# ADC.net
KiCad netlist of a schematic drawn in Altium Designer
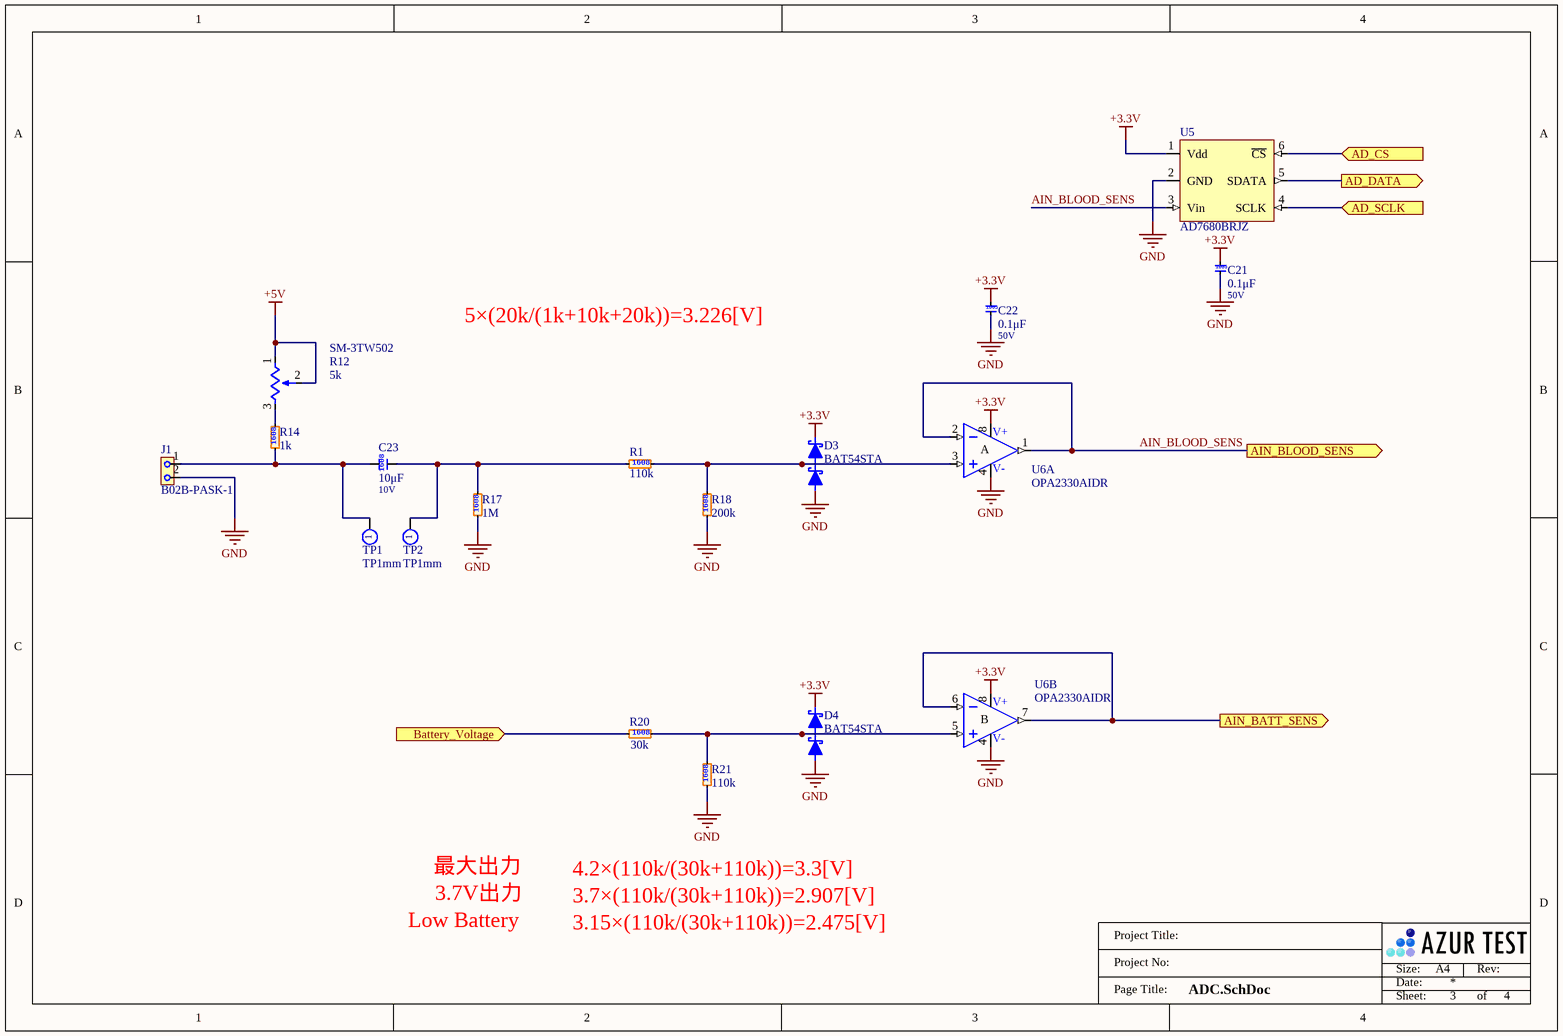
[diagram p0: ADC.SchDoc]

(export (version "E")
  (design (tool "Eeschema 10.0.6"))
  (components
    (comp (ref "C21")
      (value "GRM1552C1H101J")
      (footprint "C1005")
      (description "セラコン1005サイズ")
      (fields (field (name "TAG") "0.1μF") (field (name "VOLTAGE") "50V"))
      (libsource (lib "SSST") (part "C1005"))
    )
    (comp (ref "C22")
      (value "GRM1552C1H101J")
      (footprint "C1005")
      (description "セラコン1005サイズ")
      (fields (field (name "TAG") "0.1μF") (field (name "VOLTAGE") "50V"))
      (libsource (lib "SSST") (part "C1005"))
    )
    (comp (ref "C23")
      (value "C1608X5R1A106M080AC")
      (footprint "C1608")
      (description "セラコン1608サイズ")
      (fields (field (name "TAG") "10μF") (field (name "VOLTAGE") "10V"))
      (libsource (lib "Isoretion wear meater") (part "C1608"))
    )
    (comp (ref "D3")
      (value "BAT54STA")
      (footprint "SOT-23")
      (description "ダブル直列ショットキー")
      (libsource (lib "SSST") (part "BAT54S"))
    )
    (comp (ref "D4")
      (value "BAT54STA")
      (footprint "SOT-23")
      (description "ダブル直列ショットキー")
      (libsource (lib "SSST") (part "BAT54S"))
    )
    (comp (ref "J1")
      (value "B02B-PASK-1")
      (footprint "B02B-PASK-1")
      (description "雄,ストレート,1列2ピン")
      (libsource (lib "SSST") (part "B02B-PASK-1"))
    )
    (comp (ref "R1")
      (value "RG1608P-114-B-T5")
      (footprint "R1608")
      (description "薄膜チップ抵抗1608サイズ")
      (fields (field (name "TAG") "110k"))
      (libsource (lib "") (part "MF1608_1"))
    )
    (comp (ref "R12")
      (value "SM-3TW502")
      (footprint "SM-3TW")
      (description "CERMET TRIMMER 11 turns Top adjustmet")
      (fields (field (name "TAG") "5k"))
      (libsource (lib "SSST") (part "SM-3TW***"))
    )
    (comp (ref "R14")
      (value "RG1608P-102-B-T5")
      (footprint "R1608")
      (description "薄膜チップ抵抗1608サイズ")
      (fields (field (name "TAG") "1k"))
      (libsource (lib "SSST") (part "MF1608"))
    )
    (comp (ref "R17")
      (value "RT0603DRD071ML")
      (footprint "R1608")
      (description "薄膜チップ抵抗1608サイズ")
      (fields (field (name "TAG") "1M"))
      (libsource (lib "SSST") (part "MF1608"))
    )
    (comp (ref "R18")
      (value "RG1608P-204-B-T5")
      (footprint "R1608")
      (description "薄膜チップ抵抗1608サイズ")
      (fields (field (name "TAG") "200k"))
      (libsource (lib "SSST") (part "MF1608"))
    )
    (comp (ref "R20")
      (value "RG1608P-303-B-T5")
      (footprint "R1608")
      (description "薄膜チップ抵抗1608サイズ")
      (fields (field (name "TAG") "30k"))
      (libsource (lib "") (part "MF1608_1"))
    )
    (comp (ref "R21")
      (value "RG1608P-114-B-T5")
      (footprint "R1608")
      (description "薄膜チップ抵抗1608サイズ")
      (fields (field (name "TAG") "110k"))
      (libsource (lib "SSST") (part "MF1608"))
    )
    (comp (ref "TP1")
      (value "TP1mm")
      (footprint "TP1mm")
      (description "Test-Point 1mm")
      (libsource (lib "SSST") (part "TP1mm"))
    )
    (comp (ref "TP2")
      (value "TP1mm")
      (footprint "TP1mm")
      (description "Test-Point 1mm")
      (libsource (lib "SSST") (part "TP1mm"))
    )
    (comp (ref "U5")
      (value "AD7680BRJZ")
      (footprint "SOT-23-6")
      (description "16bit ADC 2.5V～5.5V SOT23")
      (libsource (lib "SSST") (part "AD7680BRJZ"))
    )
    (comp (ref "U6")
      (value "OPA2330AIDR")
      (footprint "SOIC8_3.9mm")
      (description "CMOS ゼロドリフトアンプ 2回路 レールツーレール 8SOIC")
      (libsource (lib "SSST") (part "OPA2330AIDR"))
    )
  )
  (nets
    (net (code "1") (name "+3.3V") (class "Default")
      (node (ref "C21") (pin "2") (pinfunction "2_2") (pintype "passive"))
      (node (ref "C22") (pin "2") (pinfunction "2_2") (pintype "passive"))
      (node (ref "D3") (pin "2") (pinfunction "K_2") (pintype "passive"))
      (node (ref "D4") (pin "2") (pinfunction "K_2") (pintype "passive"))
      (node (ref "U5") (pin "1") (pinfunction "Vdd_1") (pintype "power_in"))
      (node (ref "U6") (pin "8") (pinfunction "V+_8") (pintype "power_in"))
    )
    (net (code "2") (name "+5V") (class "Default")
      (node (ref "R12") (pin "1") (pinfunction "1_1") (pintype "passive"))
      (node (ref "R12") (pin "2") (pinfunction "2_2") (pintype "passive"))
    )
    (net (code "3") (name "/AD_CS") (class "Default")
      (node (ref "U5") (pin "6") (pinfunction "~{CS}_6") (pintype "input"))
    )
    (net (code "4") (name "/AD_DATA") (class "Default")
      (node (ref "U5") (pin "5") (pinfunction "SDATA_5") (pintype "output"))
    )
    (net (code "5") (name "/AD_SCLK") (class "Default")
      (node (ref "U5") (pin "4") (pinfunction "SCLK_4") (pintype "input"))
    )
    (net (code "6") (name "/AIN_BATT_SENS") (class "Default")
      (node (ref "U6") (pin "6") (pinfunction "IN-_6") (pintype "input"))
      (node (ref "U6") (pin "7") (pinfunction "OUT_7") (pintype "output"))
    )
    (net (code "7") (name "/AIN_BLOOD_SENS") (class "Default")
      (node (ref "U5") (pin "3") (pinfunction "Vin_3") (pintype "input"))
      (node (ref "U6") (pin "1") (pinfunction "OUT_1") (pintype "output"))
      (node (ref "U6") (pin "2") (pinfunction "IN-_2") (pintype "input"))
    )
    (net (code "8") (name "/Battery_Voltage") (class "Default")
      (node (ref "R20") (pin "1") (pinfunction "1_1") (pintype "passive"))
    )
    (net (code "9") (name "GND") (class "Default")
      (node (ref "C21") (pin "1") (pinfunction "1_1") (pintype "passive"))
      (node (ref "C22") (pin "1") (pinfunction "1_1") (pintype "passive"))
      (node (ref "D3") (pin "1") (pinfunction "A_1") (pintype "passive"))
      (node (ref "D4") (pin "1") (pinfunction "A_1") (pintype "passive"))
      (node (ref "J1") (pin "2") (pinfunction "2_2") (pintype "passive"))
      (node (ref "R17") (pin "1") (pinfunction "1_1") (pintype "passive"))
      (node (ref "R18") (pin "1") (pinfunction "1_1") (pintype "passive"))
      (node (ref "R21") (pin "1") (pinfunction "1_1") (pintype "passive"))
      (node (ref "U5") (pin "2") (pinfunction "GND_2") (pintype "power_in"))
      (node (ref "U6") (pin "4") (pinfunction "V-_4") (pintype "power_in"))
    )
    (net (code "10") (name "Net-(C23-Pad1)") (class "Default")
      (node (ref "C23") (pin "1") (pinfunction "1_1") (pintype "passive"))
      (node (ref "R1") (pin "1") (pinfunction "1_1") (pintype "passive"))
      (node (ref "R17") (pin "2") (pinfunction "2_2") (pintype "passive"))
      (node (ref "TP2") (pin "1") (pinfunction "1_1") (pintype "passive"))
    )
    (net (code "11") (name "Net-(C23-Pad2)") (class "Default")
      (node (ref "C23") (pin "2") (pinfunction "2_2") (pintype "passive"))
      (node (ref "J1") (pin "1") (pinfunction "1_1") (pintype "passive"))
      (node (ref "R14") (pin "1") (pinfunction "1_1") (pintype "passive"))
      (node (ref "TP1") (pin "1") (pinfunction "1_1") (pintype "passive"))
    )
    (net (code "12") (name "Net-(D3-C)") (class "Default")
      (node (ref "D3") (pin "3") (pinfunction "C_3") (pintype "passive"))
      (node (ref "R1") (pin "2") (pinfunction "2_2") (pintype "passive"))
      (node (ref "R18") (pin "2") (pinfunction "2_2") (pintype "passive"))
      (node (ref "U6") (pin "3") (pinfunction "IN+_3") (pintype "input"))
    )
    (net (code "13") (name "Net-(D4-C)") (class "Default")
      (node (ref "D4") (pin "3") (pinfunction "C_3") (pintype "passive"))
      (node (ref "R20") (pin "2") (pinfunction "2_2") (pintype "passive"))
      (node (ref "R21") (pin "2") (pinfunction "2_2") (pintype "passive"))
      (node (ref "U6") (pin "5") (pinfunction "IN+_5") (pintype "input"))
    )
    (net (code "14") (name "Net-(R12-Pad3)") (class "Default")
      (node (ref "R12") (pin "3") (pinfunction "3_3") (pintype "passive"))
      (node (ref "R14") (pin "2") (pinfunction "2_2") (pintype "passive"))
    )
  )
)
